# LPCB282_-_TOP.net
KiCad netlist of a schematic drawn in Altium Designer
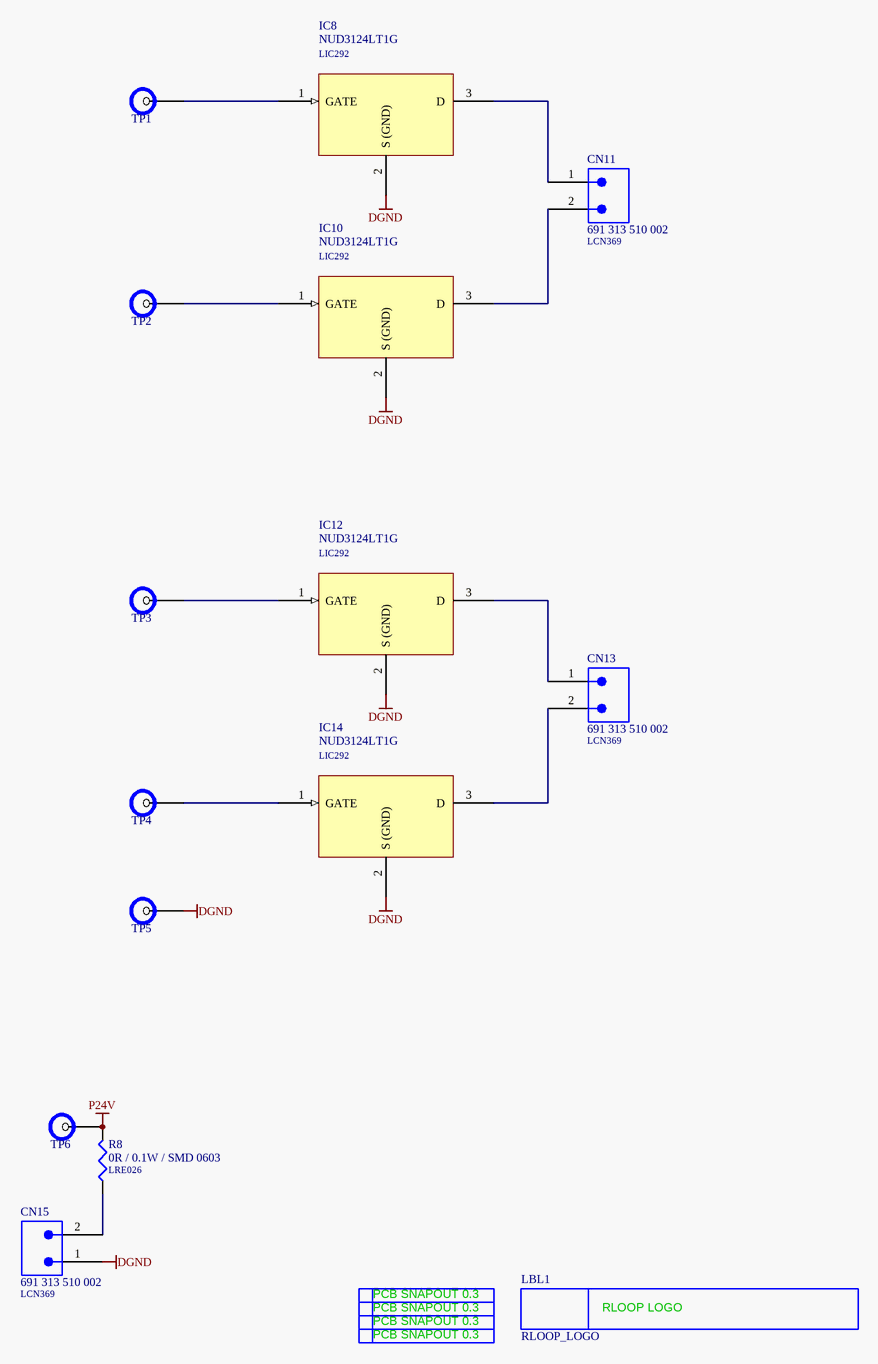
[diagram p0: LPCB282 - TOP.SchDoc]

(export (version "E")
  (design (tool "Eeschema 10.0.6"))
  (components
    (comp (ref "CN11")
      (value "691 313 510 002")
      (footprint "691 313 510 002")
      (description "Connector, Pluggable Terminal Block, 5.08mm, 2 Way, PTH")
      (fields (field (name "LDL_NUMBER") "LCN369"))
      (libsource (lib "LDL_Connectors") (part "691 313 510 002"))
    )
    (comp (ref "CN13")
      (value "691 313 510 002")
      (footprint "691 313 510 002")
      (description "Connector, Pluggable Terminal Block, 5.08mm, 2 Way, PTH")
      (fields (field (name "LDL_NUMBER") "LCN369"))
      (libsource (lib "LDL_Connectors") (part "691 313 510 002"))
    )
    (comp (ref "CN15")
      (value "691 313 510 002")
      (footprint "691 313 510 002")
      (description "Connector, Pluggable Terminal Block, 5.08mm, 2 Way, PTH")
      (fields (field (name "LDL_NUMBER") "LCN369"))
      (libsource (lib "LDL_Connectors") (part "691 313 510 002"))
    )
    (comp (ref "IC8")
      (value "NUD3124LT1G")
      (footprint "LFP021__SOT23")
      (description "IC, Relay Driver, 28V Industrial, SMD SOT23 [LIC292]")
      (fields (field (name "LDL_NUMBER") "LIC292"))
      (libsource (lib "LDL_Semiconductors") (part "NUD3124LT1G"))
    )
    (comp (ref "IC10")
      (value "NUD3124LT1G")
      (footprint "LFP021__SOT23")
      (description "IC, Relay Driver, 28V Industrial, SMD SOT23 [LIC292]")
      (fields (field (name "LDL_NUMBER") "LIC292"))
      (libsource (lib "LDL_Semiconductors") (part "NUD3124LT1G"))
    )
    (comp (ref "IC12")
      (value "NUD3124LT1G")
      (footprint "LFP021__SOT23")
      (description "IC, Relay Driver, 28V Industrial, SMD SOT23 [LIC292]")
      (fields (field (name "LDL_NUMBER") "LIC292"))
      (libsource (lib "LDL_Semiconductors") (part "NUD3124LT1G"))
    )
    (comp (ref "IC14")
      (value "NUD3124LT1G")
      (footprint "LFP021__SOT23")
      (description "IC, Relay Driver, 28V Industrial, SMD SOT23 [LIC292]")
      (fields (field (name "LDL_NUMBER") "LIC292"))
      (libsource (lib "LDL_Semiconductors") (part "NUD3124LT1G"))
    )
    (comp (ref "LBL1")
      (value "RLOOP_LOGO")
      (footprint "RLOOP_LOGO")
      (libsource (lib "LDL_Mechanical") (part "RLOOP_LOGO"))
    )
    (comp (ref "R8")
      (value "0R / 0.1W / SMD 0603")
      (footprint "LFP020__CR1608-0603-IPC7351_B")
      (description "Resistor, Ceramic Chip, 0R, 0.1W, SMD 0603 [LRE026]")
      (fields (field (name "LDL_NUMBER") "LRE026"))
      (libsource (lib "LDL_Resistors") (part "0R / 0.1W / SMD 0603"))
    )
    (comp (ref "SN1")
      (value "PCB_SNAPOUT_0.3MM")
      (footprint "PCB_SNAPOUT_0.3MM")
      (description "PCB Snapout + 0.3mm")
      (libsource (lib "LDL_Mechanical") (part "PCB_SNAPOUT_0.3MM"))
    )
    (comp (ref "SN2")
      (value "PCB_SNAPOUT_0.3MM")
      (footprint "PCB_SNAPOUT_0.3MM")
      (description "PCB Snapout + 0.3mm")
      (libsource (lib "LDL_Mechanical") (part "PCB_SNAPOUT_0.3MM"))
    )
    (comp (ref "SN3")
      (value "PCB_SNAPOUT_0.3MM")
      (footprint "PCB_SNAPOUT_0.3MM")
      (description "PCB Snapout + 0.3mm")
      (libsource (lib "LDL_Mechanical") (part "PCB_SNAPOUT_0.3MM"))
    )
    (comp (ref "SN4")
      (value "PCB_SNAPOUT_0.3MM")
      (footprint "PCB_SNAPOUT_0.3MM")
      (description "PCB Snapout + 0.3mm")
      (libsource (lib "LDL_Mechanical") (part "PCB_SNAPOUT_0.3MM"))
    )
    (comp (ref "TP1")
      (value "SMD_TP_VIA")
      (footprint "SMD-TP-VIA")
      (description "SMD Test Point With VIA")
      (libsource (lib "LDL_Connectors") (part "SMD_TP_VIA"))
    )
    (comp (ref "TP2")
      (value "SMD_TP_VIA")
      (footprint "SMD-TP-VIA")
      (description "SMD Test Point With VIA")
      (libsource (lib "LDL_Connectors") (part "SMD_TP_VIA"))
    )
    (comp (ref "TP3")
      (value "SMD_TP_VIA")
      (footprint "SMD-TP-VIA")
      (description "SMD Test Point With VIA")
      (libsource (lib "LDL_Connectors") (part "SMD_TP_VIA"))
    )
    (comp (ref "TP4")
      (value "SMD_TP_VIA")
      (footprint "SMD-TP-VIA")
      (description "SMD Test Point With VIA")
      (libsource (lib "LDL_Connectors") (part "SMD_TP_VIA"))
    )
    (comp (ref "TP5")
      (value "SMD_TP_VIA")
      (footprint "SMD-TP-VIA")
      (description "SMD Test Point With VIA")
      (libsource (lib "LDL_Connectors") (part "SMD_TP_VIA"))
    )
    (comp (ref "TP6")
      (value "SMD_TP_VIA")
      (footprint "SMD-TP-VIA")
      (description "SMD Test Point With VIA")
      (libsource (lib "LDL_Connectors") (part "SMD_TP_VIA"))
    )
  )
  (nets
    (net (code "1") (name "DGND") (class "Default")
      (node (ref "CN15") (pin "1") (pinfunction "1_1") (pintype "passive"))
      (node (ref "IC10") (pin "2") (pinfunction "S_(GND)_2") (pintype "passive"))
      (node (ref "IC12") (pin "2") (pinfunction "S_(GND)_2") (pintype "passive"))
      (node (ref "IC14") (pin "2") (pinfunction "S_(GND)_2") (pintype "passive"))
      (node (ref "IC8") (pin "2") (pinfunction "S_(GND)_2") (pintype "passive"))
      (node (ref "TP5") (pin "1") (pintype "passive"))
    )
    (net (code "2") (name "Net-(CN15-Pad2)") (class "Default")
      (node (ref "CN15") (pin "2") (pinfunction "2_2") (pintype "passive"))
      (node (ref "R8") (pin "1") (pintype "passive"))
    )
    (net (code "3") (name "Net-(IC8-D)") (class "Default")
      (node (ref "CN11") (pin "1") (pinfunction "1_1") (pintype "passive"))
      (node (ref "IC8") (pin "3") (pinfunction "D_3") (pintype "passive"))
    )
    (net (code "4") (name "Net-(IC8-GATE)") (class "Default")
      (node (ref "IC8") (pin "1") (pinfunction "GATE_1") (pintype "input"))
      (node (ref "TP1") (pin "1") (pintype "passive"))
    )
    (net (code "5") (name "Net-(IC10-D)") (class "Default")
      (node (ref "CN11") (pin "2") (pinfunction "2_2") (pintype "passive"))
      (node (ref "IC10") (pin "3") (pinfunction "D_3") (pintype "passive"))
    )
    (net (code "6") (name "Net-(IC10-GATE)") (class "Default")
      (node (ref "IC10") (pin "1") (pinfunction "GATE_1") (pintype "input"))
      (node (ref "TP2") (pin "1") (pintype "passive"))
    )
    (net (code "7") (name "Net-(IC12-D)") (class "Default")
      (node (ref "CN13") (pin "1") (pinfunction "1_1") (pintype "passive"))
      (node (ref "IC12") (pin "3") (pinfunction "D_3") (pintype "passive"))
    )
    (net (code "8") (name "Net-(IC12-GATE)") (class "Default")
      (node (ref "IC12") (pin "1") (pinfunction "GATE_1") (pintype "input"))
      (node (ref "TP3") (pin "1") (pintype "passive"))
    )
    (net (code "9") (name "Net-(IC14-D)") (class "Default")
      (node (ref "CN13") (pin "2") (pinfunction "2_2") (pintype "passive"))
      (node (ref "IC14") (pin "3") (pinfunction "D_3") (pintype "passive"))
    )
    (net (code "10") (name "Net-(IC14-GATE)") (class "Default")
      (node (ref "IC14") (pin "1") (pinfunction "GATE_1") (pintype "input"))
      (node (ref "TP4") (pin "1") (pintype "passive"))
    )
    (net (code "11") (name "P24V") (class "Default")
      (node (ref "R8") (pin "2") (pintype "passive"))
      (node (ref "TP6") (pin "1") (pintype "passive"))
    )
  )
)
